# owl.net
KiCad netlist of a schematic drawn in EAGLE
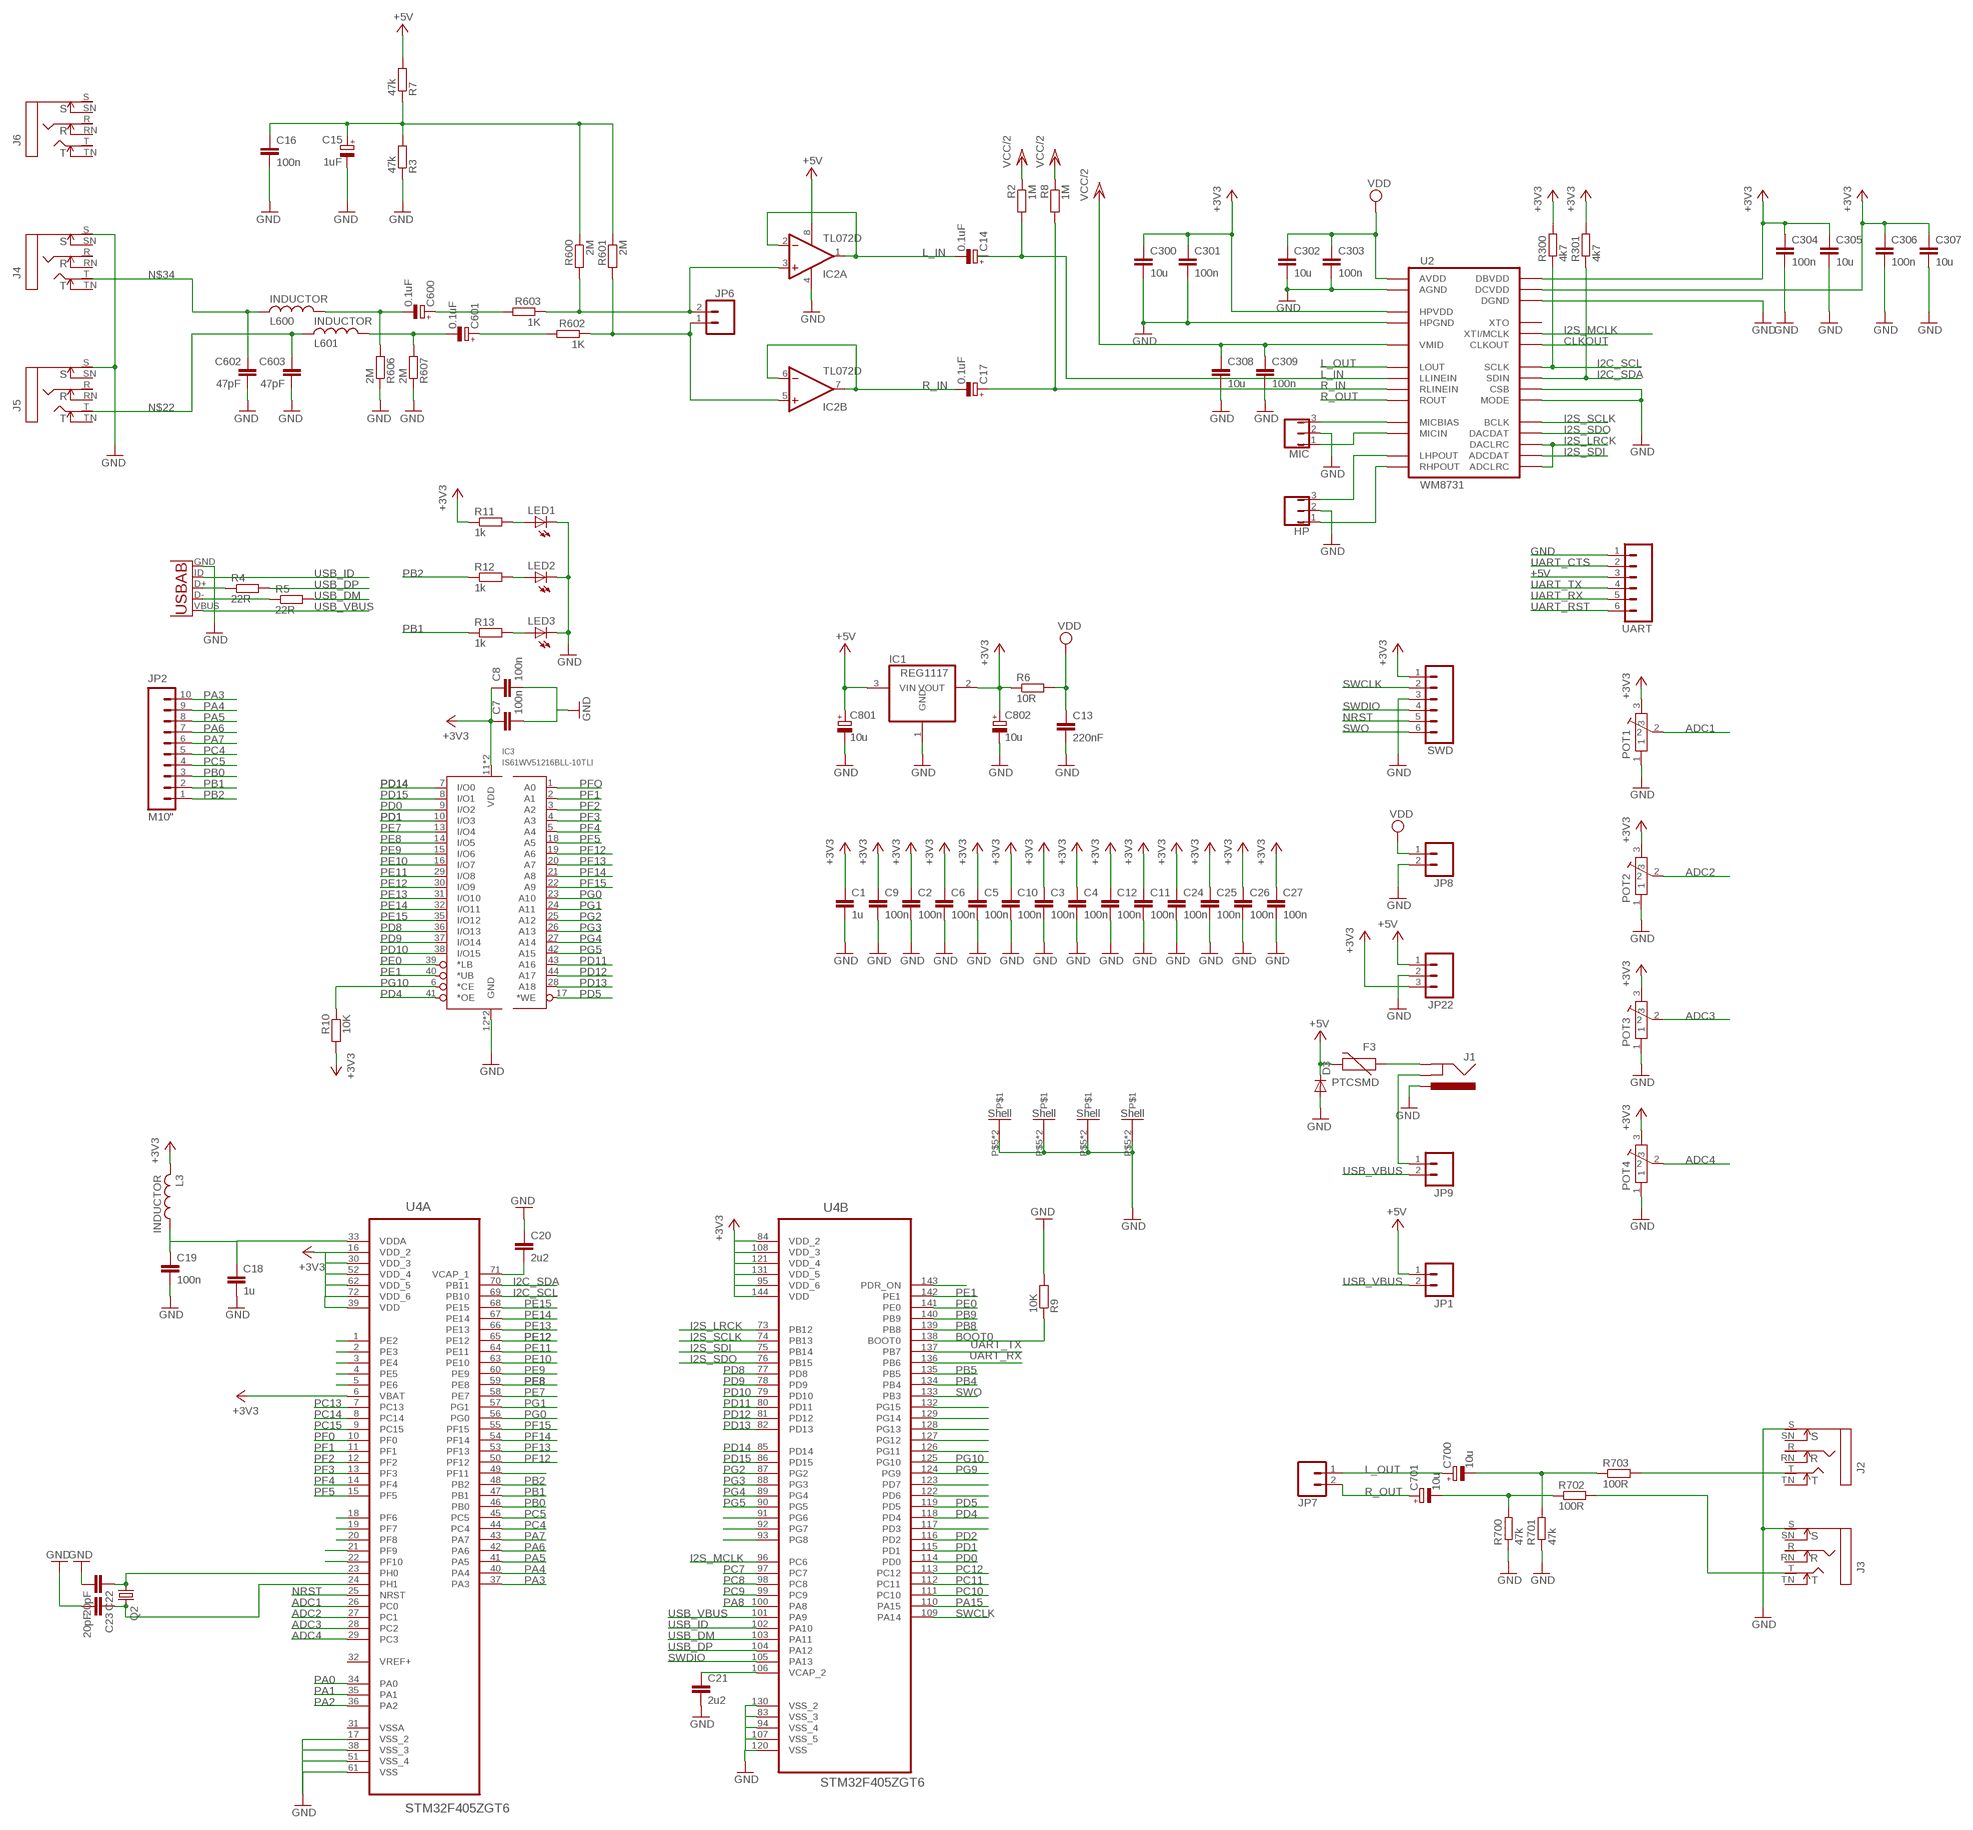
[diagram p0: schematic, sheet 1]

(export (version "E")
  (design (tool "Eeschema 10.0.6"))
  (components
    (comp (ref "C1")
      (value "1u")
      (footprint "eagle-import:C0603")
      (libsource (lib "eagle-import") (part "C-EUC0603"))
    )
    (comp (ref "C2")
      (value "100n")
      (footprint "eagle-import:C0603")
      (libsource (lib "eagle-import") (part "C-EUC0603"))
    )
    (comp (ref "C3")
      (value "100n")
      (footprint "eagle-import:C0603")
      (libsource (lib "eagle-import") (part "C-EUC0603"))
    )
    (comp (ref "C4")
      (value "100n")
      (footprint "eagle-import:C0603")
      (libsource (lib "eagle-import") (part "C-EUC0603"))
    )
    (comp (ref "C5")
      (value "100n")
      (footprint "eagle-import:C0603")
      (libsource (lib "eagle-import") (part "C-EUC0603"))
    )
    (comp (ref "C6")
      (value "100n")
      (footprint "eagle-import:C0603")
      (libsource (lib "eagle-import") (part "C-EUC0603"))
    )
    (comp (ref "C7")
      (value "100n")
      (footprint "eagle-import:C0603")
      (libsource (lib "eagle-import") (part "C-EUC0603"))
    )
    (comp (ref "C8")
      (value "100n")
      (footprint "eagle-import:C0603")
      (libsource (lib "eagle-import") (part "C-EUC0603"))
    )
    (comp (ref "C9")
      (value "100n")
      (footprint "eagle-import:C0603")
      (libsource (lib "eagle-import") (part "C-EUC0603"))
    )
    (comp (ref "C10")
      (value "100n")
      (footprint "eagle-import:C0603")
      (libsource (lib "eagle-import") (part "C-EUC0603"))
    )
    (comp (ref "C11")
      (value "100n")
      (footprint "eagle-import:C0603")
      (libsource (lib "eagle-import") (part "C-EUC0603"))
    )
    (comp (ref "C12")
      (value "100n")
      (footprint "eagle-import:C0603")
      (libsource (lib "eagle-import") (part "C-EUC0603"))
    )
    (comp (ref "C13")
      (value "220nF")
      (footprint "eagle-import:C0603")
      (libsource (lib "eagle-import") (part "C-EUC0603"))
    )
    (comp (ref "C14")
      (value "0.1uF")
      (footprint "eagle-import:PANASONIC_A")
      (libsource (lib "eagle-import") (part "CPOL-EUA"))
    )
    (comp (ref "C15")
      (value "1uF")
      (footprint "eagle-import:PANASONIC_A")
      (libsource (lib "eagle-import") (part "CPOL-EUA"))
    )
    (comp (ref "C16")
      (value "100n")
      (footprint "eagle-import:C0603")
      (libsource (lib "eagle-import") (part "C-EUC0603"))
    )
    (comp (ref "C17")
      (value "0.1uF")
      (footprint "eagle-import:PANASONIC_A")
      (libsource (lib "eagle-import") (part "CPOL-EUA"))
    )
    (comp (ref "C18")
      (value "1u")
      (footprint "eagle-import:C0603")
      (libsource (lib "eagle-import") (part "C-EUC0603"))
    )
    (comp (ref "C19")
      (value "100n")
      (footprint "eagle-import:C0603")
      (libsource (lib "eagle-import") (part "C-EUC0603"))
    )
    (comp (ref "C20")
      (value "2u2")
      (footprint "eagle-import:C0603")
      (libsource (lib "eagle-import") (part "C-EUC0603"))
    )
    (comp (ref "C21")
      (value "2u2")
      (footprint "eagle-import:C0603")
      (libsource (lib "eagle-import") (part "C-EUC0603"))
    )
    (comp (ref "C22")
      (value "20pF")
      (footprint "eagle-import:C0603")
      (libsource (lib "eagle-import") (part "C-EUC0603"))
    )
    (comp (ref "C23")
      (value "20pF")
      (footprint "eagle-import:C0603")
      (libsource (lib "eagle-import") (part "C-EUC0603"))
    )
    (comp (ref "C24")
      (value "100n")
      (footprint "eagle-import:C0603")
      (libsource (lib "eagle-import") (part "C-EUC0603"))
    )
    (comp (ref "C25")
      (value "100n")
      (footprint "eagle-import:C0603")
      (libsource (lib "eagle-import") (part "C-EUC0603"))
    )
    (comp (ref "C26")
      (value "100n")
      (footprint "eagle-import:C0603")
      (libsource (lib "eagle-import") (part "C-EUC0603"))
    )
    (comp (ref "C27")
      (value "100n")
      (footprint "eagle-import:C0603")
      (libsource (lib "eagle-import") (part "C-EUC0603"))
    )
    (comp (ref "C300")
      (value "10u")
      (footprint "eagle-import:C1206")
      (libsource (lib "eagle-import") (part "C-EUC1206"))
    )
    (comp (ref "C301")
      (value "100n")
      (footprint "eagle-import:C0603")
      (libsource (lib "eagle-import") (part "C-EUC0603"))
    )
    (comp (ref "C302")
      (value "10u")
      (footprint "eagle-import:C1206")
      (libsource (lib "eagle-import") (part "C-EUC1206"))
    )
    (comp (ref "C303")
      (value "100n")
      (footprint "eagle-import:C0603")
      (libsource (lib "eagle-import") (part "C-EUC0603"))
    )
    (comp (ref "C304")
      (value "100n")
      (footprint "eagle-import:C0603")
      (libsource (lib "eagle-import") (part "C-EUC0603"))
    )
    (comp (ref "C305")
      (value "10u")
      (footprint "eagle-import:C1206")
      (libsource (lib "eagle-import") (part "C-EUC1206"))
    )
    (comp (ref "C306")
      (value "100n")
      (footprint "eagle-import:C0603")
      (libsource (lib "eagle-import") (part "C-EUC0603"))
    )
    (comp (ref "C307")
      (value "10u")
      (footprint "eagle-import:C1206")
      (libsource (lib "eagle-import") (part "C-EUC1206"))
    )
    (comp (ref "C308")
      (value "10u")
      (footprint "eagle-import:C1206")
      (libsource (lib "eagle-import") (part "C-EUC1206"))
    )
    (comp (ref "C309")
      (value "100n")
      (footprint "eagle-import:C0603")
      (libsource (lib "eagle-import") (part "C-EUC0603"))
    )
    (comp (ref "C600")
      (value "0.1uF")
      (footprint "eagle-import:PANASONIC_A")
      (libsource (lib "eagle-import") (part "CPOL-EUA"))
    )
    (comp (ref "C601")
      (value "0.1uF")
      (footprint "eagle-import:PANASONIC_A")
      (libsource (lib "eagle-import") (part "CPOL-EUA"))
    )
    (comp (ref "C602")
      (value "47pF")
      (footprint "eagle-import:C0603")
      (libsource (lib "eagle-import") (part "C-EUC0603"))
    )
    (comp (ref "C603")
      (value "47pF")
      (footprint "eagle-import:C0603")
      (libsource (lib "eagle-import") (part "C-EUC0603"))
    )
    (comp (ref "C700")
      (value "10u")
      (footprint "eagle-import:PANASONIC_A")
      (libsource (lib "eagle-import") (part "CPOL-EUA"))
    )
    (comp (ref "C701")
      (value "10u")
      (footprint "eagle-import:PANASONIC_A")
      (libsource (lib "eagle-import") (part "CPOL-EUA"))
    )
    (comp (ref "C801")
      (value "10u")
      (footprint "eagle-import:PANASONIC_A")
      (libsource (lib "eagle-import") (part "CPOL-EUA"))
    )
    (comp (ref "C802")
      (value "10u")
      (footprint "eagle-import:PANASONIC_A")
      (libsource (lib "eagle-import") (part "CPOL-EUA"))
    )
    (comp (ref "D3")
      (value "DIODESMA")
      (footprint "eagle-import:SMA-DIODE")
      (libsource (lib "eagle-import") (part "DIODESMA"))
    )
    (comp (ref "F3")
      (value "PTCSMD")
      (footprint "eagle-import:PTC-1206")
      (libsource (lib "eagle-import") (part "PTCSMD"))
    )
    (comp (ref "HP")
      (value "JMP/3P/SIP")
      (footprint "eagle-import:JMP_3P_SIP")
      (libsource (lib "eagle-import") (part "JMP/3P/SIP"))
    )
    (comp (ref "IC1")
      (value "REG1117")
      (footprint "eagle-import:SOT223")
      (libsource (lib "eagle-import") (part "REG1117"))
    )
    (comp (ref "IC2")
      (value "TL072D")
      (footprint "eagle-import:SO08")
      (libsource (lib "eagle-import") (part "TL072D"))
    )
    (comp (ref "IC3")
      (value "IS61WV51216BLL-10TLI")
      (footprint "eagle-import:TSOP44-II")
      (libsource (lib "eagle-import") (part "IS61WV51216BLL-10TLI"))
    )
    (comp (ref "J1")
      (value "POWER_JACKPTH")
      (footprint "eagle-import:POWER_JACK_PTH")
      (libsource (lib "eagle-import") (part "POWER_JACKPTH"))
    )
    (comp (ref "J2")
      (value "NEUTRIK_NMJ6HCD2")
      (footprint "eagle-import:NMJ6HCD2")
      (libsource (lib "eagle-import") (part "NEUTRIK_NMJ6HCD2"))
    )
    (comp (ref "J3")
      (value "NEUTRIK_NMJ6HCD2")
      (footprint "eagle-import:NMJ6HCD2")
      (libsource (lib "eagle-import") (part "NEUTRIK_NMJ6HCD2"))
    )
    (comp (ref "J4")
      (value "NEUTRIK_NMJ6HCD2")
      (footprint "eagle-import:NMJ6HCD2")
      (libsource (lib "eagle-import") (part "NEUTRIK_NMJ6HCD2"))
    )
    (comp (ref "J5")
      (value "NEUTRIK_NMJ6HCD2")
      (footprint "eagle-import:NMJ6HCD2")
      (libsource (lib "eagle-import") (part "NEUTRIK_NMJ6HCD2"))
    )
    (comp (ref "J6")
      (value "NEUTRIK_NMJ6HCD2")
      (footprint "eagle-import:NMJ6HCD2")
      (libsource (lib "eagle-import") (part "NEUTRIK_NMJ6HCD2"))
    )
    (comp (ref "JP1")
      (value "M02PTH")
      (footprint "eagle-import:1X02")
      (libsource (lib "eagle-import") (part "M02PTH"))
    )
    (comp (ref "JP2")
      (value "M10\"")
      (footprint "eagle-import:1X10")
      (libsource (lib "eagle-import") (part "M10{dblquote}"))
    )
    (comp (ref "JP6")
      (value "M02PTH")
      (footprint "eagle-import:1X02")
      (libsource (lib "eagle-import") (part "M02PTH"))
    )
    (comp (ref "JP7")
      (value "M02PTH")
      (footprint "eagle-import:1X02")
      (libsource (lib "eagle-import") (part "M02PTH"))
    )
    (comp (ref "JP8")
      (value "M02PTH")
      (footprint "eagle-import:1X02")
      (libsource (lib "eagle-import") (part "M02PTH"))
    )
    (comp (ref "JP9")
      (value "M02PTH")
      (footprint "eagle-import:1X02")
      (libsource (lib "eagle-import") (part "M02PTH"))
    )
    (comp (ref "JP22")
      (value "M03PTH")
      (footprint "eagle-import:1X03")
      (libsource (lib "eagle-import") (part "M03PTH"))
    )
    (comp (ref "L3")
      (value "INDUCTOR")
      (footprint "eagle-import:0603")
      (libsource (lib "eagle-import") (part "INDUCTOR"))
    )
    (comp (ref "L600")
      (value "INDUCTOR")
      (footprint "eagle-import:0603")
      (libsource (lib "eagle-import") (part "INDUCTOR"))
    )
    (comp (ref "L601")
      (value "INDUCTOR")
      (footprint "eagle-import:0603")
      (libsource (lib "eagle-import") (part "INDUCTOR"))
    )
    (comp (ref "LED1")
      (value "LED1206")
      (footprint "eagle-import:LED-1206")
      (libsource (lib "eagle-import") (part "LED1206"))
    )
    (comp (ref "LED2")
      (value "LED1206")
      (footprint "eagle-import:LED-1206")
      (libsource (lib "eagle-import") (part "LED1206"))
    )
    (comp (ref "LED3")
      (value "LED3MM")
      (footprint "eagle-import:LED3MM")
      (libsource (lib "eagle-import") (part "LED3MM"))
    )
    (comp (ref "MIC")
      (value "JMP/3P/SIP")
      (footprint "eagle-import:JMP_3P_SIP")
      (libsource (lib "eagle-import") (part "JMP/3P/SIP"))
    )
    (comp (ref "POT1")
      (value "POT-ALPS-RK09L1140")
      (footprint "eagle-import:POT-ALPS-RK09L1140")
      (libsource (lib "eagle-import") (part "POT-ALPS-RK09L1140"))
    )
    (comp (ref "POT2")
      (value "POT-ALPS-RK09L1140")
      (footprint "eagle-import:POT-ALPS-RK09L1140")
      (libsource (lib "eagle-import") (part "POT-ALPS-RK09L1140"))
    )
    (comp (ref "POT3")
      (value "POT-ALPS-RK09L1140")
      (footprint "eagle-import:POT-ALPS-RK09L1140")
      (libsource (lib "eagle-import") (part "POT-ALPS-RK09L1140"))
    )
    (comp (ref "POT4")
      (value "POT-ALPS-RK09L1140")
      (footprint "eagle-import:POT-ALPS-RK09L1140")
      (libsource (lib "eagle-import") (part "POT-ALPS-RK09L1140"))
    )
    (comp (ref "Q2")
      (value "CRYSTALHC49UP")
      (footprint "eagle-import:HC49UP")
      (libsource (lib "eagle-import") (part "CRYSTALHC49UP"))
    )
    (comp (ref "R2")
      (value "1M")
      (footprint "eagle-import:R0603")
      (libsource (lib "eagle-import") (part "R-EU_R0603"))
    )
    (comp (ref "R3")
      (value "47k")
      (footprint "eagle-import:R0603")
      (libsource (lib "eagle-import") (part "R-EU_R0603"))
    )
    (comp (ref "R4")
      (value "22R")
      (footprint "eagle-import:R0603")
      (libsource (lib "eagle-import") (part "R-EU_R0603"))
    )
    (comp (ref "R5")
      (value "22R")
      (footprint "eagle-import:R0603")
      (libsource (lib "eagle-import") (part "R-EU_R0603"))
    )
    (comp (ref "R6")
      (value "10R")
      (footprint "eagle-import:R0603")
      (libsource (lib "eagle-import") (part "R-EU_R0603"))
    )
    (comp (ref "R7")
      (value "47k")
      (footprint "eagle-import:R0603")
      (libsource (lib "eagle-import") (part "R-EU_R0603"))
    )
    (comp (ref "R8")
      (value "1M")
      (footprint "eagle-import:R0603")
      (libsource (lib "eagle-import") (part "R-EU_R0603"))
    )
    (comp (ref "R9")
      (value "10K")
      (footprint "eagle-import:R0603")
      (libsource (lib "eagle-import") (part "R-EU_R0603"))
    )
    (comp (ref "R10")
      (value "10K")
      (footprint "eagle-import:R0603")
      (libsource (lib "eagle-import") (part "R-EU_R0603"))
    )
    (comp (ref "R11")
      (value "1k")
      (footprint "eagle-import:R0603")
      (libsource (lib "eagle-import") (part "R-EU_R0603"))
    )
    (comp (ref "R12")
      (value "1k")
      (footprint "eagle-import:R0603")
      (libsource (lib "eagle-import") (part "R-EU_R0603"))
    )
    (comp (ref "R13")
      (value "1k")
      (footprint "eagle-import:R0603")
      (libsource (lib "eagle-import") (part "R-EU_R0603"))
    )
    (comp (ref "R300")
      (value "4k7")
      (footprint "eagle-import:R0603")
      (libsource (lib "eagle-import") (part "R-EU_R0603"))
    )
    (comp (ref "R301")
      (value "4k7")
      (footprint "eagle-import:R0603")
      (libsource (lib "eagle-import") (part "R-EU_R0603"))
    )
    (comp (ref "R600")
      (value "2M")
      (footprint "eagle-import:R0603")
      (libsource (lib "eagle-import") (part "R-EU_R0603"))
    )
    (comp (ref "R601")
      (value "2M")
      (footprint "eagle-import:R0603")
      (libsource (lib "eagle-import") (part "R-EU_R0603"))
    )
    (comp (ref "R602")
      (value "1K")
      (footprint "eagle-import:R0603")
      (libsource (lib "eagle-import") (part "R-EU_R0603"))
    )
    (comp (ref "R603")
      (value "1K")
      (footprint "eagle-import:R0603")
      (libsource (lib "eagle-import") (part "R-EU_R0603"))
    )
    (comp (ref "R606")
      (value "2M")
      (footprint "eagle-import:R0603")
      (libsource (lib "eagle-import") (part "R-EU_R0603"))
    )
    (comp (ref "R607")
      (value "2M")
      (footprint "eagle-import:R0603")
      (libsource (lib "eagle-import") (part "R-EU_R0603"))
    )
    (comp (ref "R700")
      (value "47k")
      (footprint "eagle-import:R0603")
      (libsource (lib "eagle-import") (part "R-EU_R0603"))
    )
    (comp (ref "R701")
      (value "47k")
      (footprint "eagle-import:R0603")
      (libsource (lib "eagle-import") (part "R-EU_R0603"))
    )
    (comp (ref "R702")
      (value "100R")
      (footprint "eagle-import:R0603")
      (libsource (lib "eagle-import") (part "R-EU_R0603"))
    )
    (comp (ref "R703")
      (value "100R")
      (footprint "eagle-import:R0603")
      (libsource (lib "eagle-import") (part "R-EU_R0603"))
    )
    (comp (ref "SWD")
      (value "M06SIP")
      (footprint "eagle-import:1X06")
      (libsource (lib "eagle-import") (part "M06SIP"))
    )
    (comp (ref "U2")
      (value "WM8731")
      (footprint "eagle-import:28-SSOP")
      (libsource (lib "eagle-import") (part "WM8731"))
    )
    (comp (ref "U3")
      (value "USB-AB")
      (footprint "eagle-import:USB-AB-MICRO-SMD")
      (libsource (lib "eagle-import") (part "USB-AB"))
    )
    (comp (ref "U4")
      (value "STM32F405ZGT6")
      (footprint "eagle-import:QFP50P2200X2200X160-144N")
      (libsource (lib "eagle-import") (part "STM32F405ZGT6"))
    )
    (comp (ref "UART")
      (value "M06SIP")
      (footprint "eagle-import:1X06")
      (libsource (lib "eagle-import") (part "M06SIP"))
    )
  )
  (nets
    (net (code "1") (name "+3V3") (class "Default")
      (node (ref "C1") (pin "1") (pinfunction "1_1") (pintype "passive"))
      (node (ref "C10") (pin "1") (pinfunction "1_1") (pintype "passive"))
      (node (ref "C11") (pin "1") (pinfunction "1_1") (pintype "passive"))
      (node (ref "C12") (pin "1") (pinfunction "1_1") (pintype "passive"))
      (node (ref "C2") (pin "1") (pinfunction "1_1") (pintype "passive"))
      (node (ref "C24") (pin "1") (pinfunction "1_1") (pintype "passive"))
      (node (ref "C25") (pin "1") (pinfunction "1_1") (pintype "passive"))
      (node (ref "C26") (pin "1") (pinfunction "1_1") (pintype "passive"))
      (node (ref "C27") (pin "1") (pinfunction "1_1") (pintype "passive"))
      (node (ref "C3") (pin "1") (pinfunction "1_1") (pintype "passive"))
      (node (ref "C300") (pin "1") (pinfunction "1_1") (pintype "passive"))
      (node (ref "C301") (pin "1") (pinfunction "1_1") (pintype "passive"))
      (node (ref "C304") (pin "1") (pinfunction "1_1") (pintype "passive"))
      (node (ref "C305") (pin "1") (pinfunction "1_1") (pintype "passive"))
      (node (ref "C306") (pin "1") (pinfunction "1_1") (pintype "passive"))
      (node (ref "C307") (pin "1") (pinfunction "1_1") (pintype "passive"))
      (node (ref "C4") (pin "1") (pinfunction "1_1") (pintype "passive"))
      (node (ref "C5") (pin "1") (pinfunction "1_1") (pintype "passive"))
      (node (ref "C6") (pin "1") (pinfunction "1_1") (pintype "passive"))
      (node (ref "C7") (pin "1") (pinfunction "1_1") (pintype "passive"))
      (node (ref "C8") (pin "1") (pinfunction "1_1") (pintype "passive"))
      (node (ref "C802") (pin "+") (pinfunction "+_+") (pintype "passive"))
      (node (ref "C9") (pin "1") (pinfunction "1_1") (pintype "passive"))
      (node (ref "IC1") (pin "2") (pinfunction "VOUT_2") (pintype "output"))
      (node (ref "IC3") (pin "11") (pinfunction "VDD_11") (pintype "power_in"))
      (node (ref "IC3") (pin "33") (pinfunction "VDD_33") (pintype "power_in"))
      (node (ref "JP22") (pin "3") (pinfunction "3_3") (pintype "passive"))
      (node (ref "L3") (pin "2") (pinfunction "2_2") (pintype "passive"))
      (node (ref "POT1") (pin "3") (pinfunction "3_3") (pintype "bidirectional"))
      (node (ref "POT2") (pin "3") (pinfunction "3_3") (pintype "bidirectional"))
      (node (ref "POT3") (pin "3") (pinfunction "3_3") (pintype "bidirectional"))
      (node (ref "POT4") (pin "3") (pinfunction "3_3") (pintype "bidirectional"))
      (node (ref "R10") (pin "2") (pinfunction "2_2") (pintype "passive"))
      (node (ref "R11") (pin "1") (pinfunction "1_1") (pintype "passive"))
      (node (ref "R300") (pin "2") (pinfunction "2_2") (pintype "passive"))
      (node (ref "R301") (pin "2") (pinfunction "2_2") (pintype "passive"))
      (node (ref "R6") (pin "1") (pinfunction "1_1") (pintype "passive"))
      (node (ref "SWD") (pin "1") (pinfunction "1_1") (pintype "passive"))
      (node (ref "U2") (pin "P$1") (pinfunction "DBVDD_P$1") (pintype "power_in"))
      (node (ref "U2") (pin "P$27") (pinfunction "DCVDD_P$27") (pintype "power_in"))
      (node (ref "U2") (pin "P$8") (pinfunction "HPVDD_P$8") (pintype "power_in"))
      (node (ref "U4") (pin "108") (pinfunction "VDD_3_108") (pintype "power_in"))
      (node (ref "U4") (pin "121") (pinfunction "VDD_4_121") (pintype "power_in"))
      (node (ref "U4") (pin "131") (pinfunction "VDD_5_131") (pintype "power_in"))
      (node (ref "U4") (pin "144") (pinfunction "VDD_144") (pintype "power_in"))
      (node (ref "U4") (pin "16") (pinfunction "VDD_2_16") (pintype "power_in"))
      (node (ref "U4") (pin "30") (pinfunction "VDD_3_30") (pintype "power_in"))
      (node (ref "U4") (pin "39") (pinfunction "VDD_39") (pintype "power_in"))
      (node (ref "U4") (pin "52") (pinfunction "VDD_4_52") (pintype "power_in"))
      (node (ref "U4") (pin "6") (pinfunction "VBAT_6") (pintype "passive"))
      (node (ref "U4") (pin "62") (pinfunction "VDD_5_62") (pintype "power_in"))
      (node (ref "U4") (pin "72") (pinfunction "VDD_6_72") (pintype "power_in"))
      (node (ref "U4") (pin "84") (pinfunction "VDD_2_84") (pintype "power_in"))
      (node (ref "U4") (pin "95") (pinfunction "VDD_6_95") (pintype "power_in"))
    )
    (net (code "2") (name "+5V") (class "Default")
      (node (ref "C801") (pin "+") (pinfunction "+_+") (pintype "passive"))
      (node (ref "D3") (pin "C") (pinfunction "C_C") (pintype "passive"))
      (node (ref "F3") (pin "2") (pinfunction "2_2") (pintype "bidirectional"))
      (node (ref "IC1") (pin "3") (pinfunction "VIN_3") (pintype "input"))
      (node (ref "IC2") (pin "8") (pinfunction "V+_8") (pintype "power_in"))
      (node (ref "JP1") (pin "1") (pinfunction "1_1") (pintype "passive"))
      (node (ref "JP22") (pin "1") (pinfunction "1_1") (pintype "passive"))
      (node (ref "R7") (pin "2") (pinfunction "2_2") (pintype "passive"))
      (node (ref "UART") (pin "3") (pinfunction "3_3") (pintype "passive"))
    )
    (net (code "3") (name "/ADC1") (class "Default")
      (node (ref "POT1") (pin "2") (pinfunction "2_2") (pintype "bidirectional"))
      (node (ref "U4") (pin "26") (pinfunction "PC0_26") (pintype "bidirectional"))
    )
    (net (code "4") (name "/ADC2") (class "Default")
      (node (ref "POT2") (pin "2") (pinfunction "2_2") (pintype "bidirectional"))
      (node (ref "U4") (pin "27") (pinfunction "PC1_27") (pintype "bidirectional"))
    )
    (net (code "5") (name "/ADC3") (class "Default")
      (node (ref "POT3") (pin "2") (pinfunction "2_2") (pintype "bidirectional"))
      (node (ref "U4") (pin "28") (pinfunction "PC2_28") (pintype "bidirectional"))
    )
    (net (code "6") (name "/ADC4") (class "Default")
      (node (ref "POT4") (pin "2") (pinfunction "2_2") (pintype "bidirectional"))
      (node (ref "U4") (pin "29") (pinfunction "PC3_29") (pintype "bidirectional"))
    )
    (net (code "7") (name "/BOOT0") (class "Default")
      (node (ref "R9") (pin "1") (pinfunction "1_1") (pintype "passive"))
      (node (ref "U4") (pin "138") (pinfunction "BOOT0_138") (pintype "passive"))
    )
    (net (code "8") (name "/CLKOUT") (class "Default")
      (node (ref "U2") (pin "P$2") (pinfunction "CLKOUT_P$2") (pintype "output"))
    )
    (net (code "9") (name "/I2C_SCL") (class "Default")
      (node (ref "R300") (pin "1") (pinfunction "1_1") (pintype "passive"))
      (node (ref "U2") (pin "P$24") (pinfunction "SCLK_P$24") (pintype "input"))
      (node (ref "U4") (pin "69") (pinfunction "PB10_69") (pintype "bidirectional"))
    )
    (net (code "10") (name "/I2C_SDA") (class "Default")
      (node (ref "R301") (pin "1") (pinfunction "1_1") (pintype "passive"))
      (node (ref "U2") (pin "P$23") (pinfunction "SDIN_P$23") (pintype "bidirectional"))
      (node (ref "U4") (pin "70") (pinfunction "PB11_70") (pintype "bidirectional"))
    )
    (net (code "11") (name "/I2S_LRCK") (class "Default")
      (node (ref "U2") (pin "P$5") (pinfunction "DACLRC_P$5") (pintype "bidirectional"))
      (node (ref "U2") (pin "P$7") (pinfunction "ADCLRC_P$7") (pintype "bidirectional"))
      (node (ref "U4") (pin "73") (pinfunction "PB12_73") (pintype "bidirectional"))
    )
    (net (code "12") (name "/I2S_MCLK") (class "Default")
      (node (ref "U2") (pin "P$25") (pinfunction "XTI/MCLK_P$25") (pintype "input"))
      (node (ref "U4") (pin "96") (pinfunction "PC6_96") (pintype "bidirectional"))
    )
    (net (code "13") (name "/I2S_SCLK") (class "Default")
      (node (ref "U2") (pin "P$3") (pinfunction "BCLK_P$3") (pintype "bidirectional"))
      (node (ref "U4") (pin "74") (pinfunction "PB13_74") (pintype "bidirectional"))
    )
    (net (code "14") (name "/I2S_SDI") (class "Default")
      (node (ref "U2") (pin "P$6") (pinfunction "ADCDAT_P$6") (pintype "output"))
      (node (ref "U4") (pin "75") (pinfunction "PB14_75") (pintype "bidirectional"))
    )
    (net (code "15") (name "/I2S_SDO") (class "Default")
      (node (ref "U2") (pin "P$4") (pinfunction "DACDAT_P$4") (pintype "input"))
      (node (ref "U4") (pin "76") (pinfunction "PB15_76") (pintype "bidirectional"))
    )
    (net (code "16") (name "/L_IN") (class "Default")
      (node (ref "C14") (pin "-") (pinfunction "-_-") (pintype "passive"))
      (node (ref "IC2") (pin "1") (pinfunction "OUT_1") (pintype "output"))
      (node (ref "IC2") (pin "2") (pinfunction "-IN_2") (pintype "input"))
      (node (ref "R2") (pin "2") (pinfunction "2_2") (pintype "passive"))
      (node (ref "U2") (pin "P$20") (pinfunction "LLINEIN_P$20") (pintype "input"))
    )
    (net (code "17") (name "/L_OUT") (class "Default")
      (node (ref "C700") (pin "+") (pinfunction "+_+") (pintype "passive"))
      (node (ref "JP7") (pin "1") (pinfunction "1_1") (pintype "passive"))
      (node (ref "U2") (pin "P$12") (pinfunction "LOUT_P$12") (pintype "output"))
    )
    (net (code "18") (name "/N$22") (class "Default")
      (node (ref "C603") (pin "1") (pinfunction "1_1") (pintype "passive"))
      (node (ref "J5") (pin "T") (pinfunction "T_T") (pintype "passive"))
      (node (ref "L601") (pin "2") (pinfunction "2_2") (pintype "passive"))
    )
    (net (code "19") (name "/N$34") (class "Default")
      (node (ref "C602") (pin "1") (pinfunction "1_1") (pintype "passive"))
      (node (ref "J4") (pin "T") (pinfunction "T_T") (pintype "passive"))
      (node (ref "L600") (pin "2") (pinfunction "2_2") (pintype "passive"))
    )
    (net (code "20") (name "/NRST") (class "Default")
      (node (ref "SWD") (pin "5") (pinfunction "5_5") (pintype "passive"))
      (node (ref "U4") (pin "25") (pinfunction "NRST_25") (pintype "passive"))
    )
    (net (code "21") (name "/PA0") (class "Default")
      (node (ref "U4") (pin "34") (pinfunction "PA0_34") (pintype "bidirectional"))
    )
    (net (code "22") (name "/PA1") (class "Default")
      (node (ref "U4") (pin "35") (pinfunction "PA1_35") (pintype "bidirectional"))
    )
    (net (code "23") (name "/PA2") (class "Default")
      (node (ref "U4") (pin "36") (pinfunction "PA2_36") (pintype "bidirectional"))
    )
    (net (code "24") (name "/PA3") (class "Default")
      (node (ref "JP2") (pin "10") (pinfunction "10_10") (pintype "passive"))
      (node (ref "U4") (pin "37") (pinfunction "PA3_37") (pintype "bidirectional"))
    )
    (net (code "25") (name "/PA4") (class "Default")
      (node (ref "JP2") (pin "9") (pinfunction "9_9") (pintype "passive"))
      (node (ref "U4") (pin "40") (pinfunction "PA4_40") (pintype "bidirectional"))
    )
    (net (code "26") (name "/PA5") (class "Default")
      (node (ref "JP2") (pin "8") (pinfunction "8_8") (pintype "passive"))
      (node (ref "U4") (pin "41") (pinfunction "PA5_41") (pintype "bidirectional"))
    )
    (net (code "27") (name "/PA6") (class "Default")
      (node (ref "JP2") (pin "7") (pinfunction "7_7") (pintype "passive"))
      (node (ref "U4") (pin "42") (pinfunction "PA6_42") (pintype "bidirectional"))
    )
    (net (code "28") (name "/PA7") (class "Default")
      (node (ref "JP2") (pin "6") (pinfunction "6_6") (pintype "passive"))
      (node (ref "U4") (pin "43") (pinfunction "PA7_43") (pintype "bidirectional"))
    )
    (net (code "29") (name "/PA8") (class "Default")
      (node (ref "U4") (pin "100") (pinfunction "PA8_100") (pintype "bidirectional"))
    )
    (net (code "30") (name "/PA15") (class "Default")
      (node (ref "U4") (pin "110") (pinfunction "PA15_110") (pintype "bidirectional"))
    )
    (net (code "31") (name "/PB0") (class "Default")
      (node (ref "JP2") (pin "3") (pinfunction "3_3") (pintype "passive"))
      (node (ref "U4") (pin "46") (pinfunction "PB0_46") (pintype "bidirectional"))
    )
    (net (code "32") (name "/PB1") (class "Default")
      (node (ref "JP2") (pin "2") (pinfunction "2_2") (pintype "passive"))
      (node (ref "R13") (pin "1") (pinfunction "1_1") (pintype "passive"))
      (node (ref "U4") (pin "47") (pinfunction "PB1_47") (pintype "bidirectional"))
    )
    (net (code "33") (name "/PB2") (class "Default")
      (node (ref "JP2") (pin "1") (pinfunction "1_1") (pintype "passive"))
      (node (ref "R12") (pin "1") (pinfunction "1_1") (pintype "passive"))
      (node (ref "U4") (pin "48") (pinfunction "PB2_48") (pintype "bidirectional"))
    )
    (net (code "34") (name "/PB4") (class "Default")
      (node (ref "U4") (pin "134") (pinfunction "PB4_134") (pintype "bidirectional"))
    )
    (net (code "35") (name "/PB5") (class "Default")
      (node (ref "U4") (pin "135") (pinfunction "PB5_135") (pintype "bidirectional"))
    )
    (net (code "36") (name "/PB8") (class "Default")
      (node (ref "U4") (pin "139") (pinfunction "PB8_139") (pintype "bidirectional"))
    )
    (net (code "37") (name "/PB9") (class "Default")
      (node (ref "U4") (pin "140") (pinfunction "PB9_140") (pintype "bidirectional"))
    )
    (net (code "38") (name "/PC4") (class "Default")
      (node (ref "JP2") (pin "5") (pinfunction "5_5") (pintype "passive"))
      (node (ref "U4") (pin "44") (pinfunction "PC4_44") (pintype "bidirectional"))
    )
    (net (code "39") (name "/PC5") (class "Default")
      (node (ref "JP2") (pin "4") (pinfunction "4_4") (pintype "passive"))
      (node (ref "U4") (pin "45") (pinfunction "PC5_45") (pintype "bidirectional"))
    )
    (net (code "40") (name "/PC7") (class "Default")
      (node (ref "U4") (pin "97") (pinfunction "PC7_97") (pintype "bidirectional"))
    )
    (net (code "41") (name "/PC8") (class "Default")
      (node (ref "U4") (pin "98") (pinfunction "PC8_98") (pintype "bidirectional"))
    )
    (net (code "42") (name "/PC9") (class "Default")
      (node (ref "U4") (pin "99") (pinfunction "PC9_99") (pintype "bidirectional"))
    )
    (net (code "43") (name "/PC10") (class "Default")
      (node (ref "U4") (pin "111") (pinfunction "PC10_111") (pintype "bidirectional"))
    )
    (net (code "44") (name "/PC11") (class "Default")
      (node (ref "U4") (pin "112") (pinfunction "PC11_112") (pintype "bidirectional"))
    )
    (net (code "45") (name "/PC12") (class "Default")
      (node (ref "U4") (pin "113") (pinfunction "PC12_113") (pintype "bidirectional"))
    )
    (net (code "46") (name "/PC13") (class "Default")
      (node (ref "U4") (pin "7") (pinfunction "PC13_7") (pintype "bidirectional"))
    )
    (net (code "47") (name "/PC14") (class "Default")
      (node (ref "U4") (pin "8") (pinfunction "PC14_8") (pintype "bidirectional"))
    )
    (net (code "48") (name "/PC15") (class "Default")
      (node (ref "U4") (pin "9") (pinfunction "PC15_9") (pintype "bidirectional"))
    )
    (net (code "49") (name "/PD0") (class "Default")
      (node (ref "IC3") (pin "9") (pinfunction "I/O2_9") (pintype "bidirectional"))
      (node (ref "U4") (pin "114") (pinfunction "PD0_114") (pintype "bidirectional"))
    )
    (net (code "50") (name "/PD1") (class "Default")
      (node (ref "IC3") (pin "10") (pinfunction "I/O3_10") (pintype "bidirectional"))
      (node (ref "U4") (pin "115") (pinfunction "PD1_115") (pintype "bidirectional"))
    )
    (net (code "51") (name "/PD2") (class "Default")
      (node (ref "U4") (pin "116") (pinfunction "PD2_116") (pintype "bidirectional"))
    )
    (net (code "52") (name "/PD4") (class "Default")
      (node (ref "IC3") (pin "41") (pinfunction "*OE_41") (pintype "bidirectional"))
      (node (ref "U4") (pin "118") (pinfunction "PD4_118") (pintype "bidirectional"))
    )
    (net (code "53") (name "/PD5") (class "Default")
      (node (ref "IC3") (pin "17") (pinfunction "*WE_17") (pintype "bidirectional"))
      (node (ref "U4") (pin "119") (pinfunction "PD5_119") (pintype "bidirectional"))
    )
    (net (code "54") (name "/PD8") (class "Default")
      (node (ref "IC3") (pin "36") (pinfunction "I/O13_36") (pintype "bidirectional"))
      (node (ref "U4") (pin "77") (pinfunction "PD8_77") (pintype "bidirectional"))
    )
    (net (code "55") (name "/PD9") (class "Default")
      (node (ref "IC3") (pin "37") (pinfunction "I/O14_37") (pintype "bidirectional"))
      (node (ref "U4") (pin "78") (pinfunction "PD9_78") (pintype "bidirectional"))
    )
    (net (code "56") (name "/PD10") (class "Default")
      (node (ref "IC3") (pin "38") (pinfunction "I/O15_38") (pintype "bidirectional"))
      (node (ref "U4") (pin "79") (pinfunction "PD10_79") (pintype "bidirectional"))
    )
    (net (code "57") (name "/PD11") (class "Default")
      (node (ref "IC3") (pin "43") (pinfunction "A16_43") (pintype "input"))
      (node (ref "U4") (pin "80") (pinfunction "PD11_80") (pintype "bidirectional"))
    )
    (net (code "58") (name "/PD12") (class "Default")
      (node (ref "IC3") (pin "44") (pinfunction "A17_44") (pintype "input"))
      (node (ref "U4") (pin "81") (pinfunction "PD12_81") (pintype "bidirectional"))
    )
    (net (code "59") (name "/PD13") (class "Default")
      (node (ref "IC3") (pin "28") (pinfunction "A18_28") (pintype "input"))
      (node (ref "U4") (pin "82") (pinfunction "PD13_82") (pintype "bidirectional"))
    )
    (net (code "60") (name "/PD14") (class "Default")
      (node (ref "IC3") (pin "7") (pinfunction "I/O0_7") (pintype "bidirectional"))
      (node (ref "U4") (pin "85") (pinfunction "PD14_85") (pintype "bidirectional"))
    )
    (net (code "61") (name "/PD15") (class "Default")
      (node (ref "IC3") (pin "8") (pinfunction "I/O1_8") (pintype "bidirectional"))
      (node (ref "U4") (pin "86") (pinfunction "PD15_86") (pintype "bidirectional"))
    )
    (net (code "62") (name "/PE0") (class "Default")
      (node (ref "IC3") (pin "39") (pinfunction "*LB_39") (pintype "bidirectional"))
      (node (ref "U4") (pin "141") (pinfunction "PE0_141") (pintype "bidirectional"))
    )
    (net (code "63") (name "/PE1") (class "Default")
      (node (ref "IC3") (pin "40") (pinfunction "*UB_40") (pintype "bidirectional"))
      (node (ref "U4") (pin "142") (pinfunction "PE1_142") (pintype "bidirectional"))
    )
    (net (code "64") (name "/PE7") (class "Default")
      (node (ref "IC3") (pin "13") (pinfunction "I/O4_13") (pintype "bidirectional"))
      (node (ref "U4") (pin "58") (pinfunction "PE7_58") (pintype "bidirectional"))
    )
    (net (code "65") (name "/PE8") (class "Default")
      (node (ref "IC3") (pin "14") (pinfunction "I/O5_14") (pintype "bidirectional"))
      (node (ref "U4") (pin "59") (pinfunction "PE8_59") (pintype "bidirectional"))
    )
    (net (code "66") (name "/PE9") (class "Default")
      (node (ref "IC3") (pin "15") (pinfunction "I/O6_15") (pintype "bidirectional"))
      (node (ref "U4") (pin "60") (pinfunction "PE9_60") (pintype "bidirectional"))
    )
    (net (code "67") (name "/PE10") (class "Default")
      (node (ref "IC3") (pin "16") (pinfunction "I/O7_16") (pintype "bidirectional"))
      (node (ref "U4") (pin "63") (pinfunction "PE10_63") (pintype "bidirectional"))
    )
    (net (code "68") (name "/PE11") (class "Default")
      (node (ref "IC3") (pin "29") (pinfunction "I/O8_29") (pintype "bidirectional"))
      (node (ref "U4") (pin "64") (pinfunction "PE11_64") (pintype "bidirectional"))
    )
    (net (code "69") (name "/PE12") (class "Default")
      (node (ref "IC3") (pin "30") (pinfunction "I/O9_30") (pintype "bidirectional"))
      (node (ref "U4") (pin "65") (pinfunction "PE12_65") (pintype "bidirectional"))
    )
    (net (code "70") (name "/PE13") (class "Default")
      (node (ref "IC3") (pin "31") (pinfunction "I/O10_31") (pintype "bidirectional"))
      (node (ref "U4") (pin "66") (pinfunction "PE13_66") (pintype "bidirectional"))
    )
    (net (code "71") (name "/PE14") (class "Default")
      (node (ref "IC3") (pin "32") (pinfunction "I/O11_32") (pintype "bidirectional"))
      (node (ref "U4") (pin "67") (pinfunction "PE14_67") (pintype "bidirectional"))
    )
    (net (code "72") (name "/PE15") (class "Default")
      (node (ref "IC3") (pin "35") (pinfunction "I/O12_35") (pintype "bidirectional"))
      (node (ref "U4") (pin "68") (pinfunction "PE15_68") (pintype "bidirectional"))
    )
    (net (code "73") (name "/PF0") (class "Default")
      (node (ref "U4") (pin "10") (pinfunction "PF0_10") (pintype "bidirectional"))
    )
    (net (code "74") (name "/PF1") (class "Default")
      (node (ref "IC3") (pin "2") (pinfunction "A1_2") (pintype "input"))
      (node (ref "U4") (pin "11") (pinfunction "PF1_11") (pintype "bidirectional"))
    )
    (net (code "75") (name "/PF2") (class "Default")
      (node (ref "IC3") (pin "3") (pinfunction "A2_3") (pintype "input"))
      (node (ref "U4") (pin "12") (pinfunction "PF2_12") (pintype "bidirectional"))
    )
    (net (code "76") (name "/PF3") (class "Default")
      (node (ref "IC3") (pin "4") (pinfunction "A3_4") (pintype "input"))
      (node (ref "U4") (pin "13") (pinfunction "PF3_13") (pintype "bidirectional"))
    )
    (net (code "77") (name "/PF4") (class "Default")
      (node (ref "IC3") (pin "5") (pinfunction "A4_5") (pintype "input"))
      (node (ref "U4") (pin "14") (pinfunction "PF4_14") (pintype "bidirectional"))
    )
    (net (code "78") (name "/PF5") (class "Default")
      (node (ref "IC3") (pin "18") (pinfunction "A5_18") (pintype "input"))
      (node (ref "U4") (pin "15") (pinfunction "PF5_15") (pintype "bidirectional"))
    )
    (net (code "79") (name "/PF12") (class "Default")
      (node (ref "IC3") (pin "19") (pinfunction "A6_19") (pintype "input"))
      (node (ref "U4") (pin "50") (pinfunction "PF12_50") (pintype "bidirectional"))
    )
    (net (code "80") (name "/PF13") (class "Default")
      (node (ref "IC3") (pin "20") (pinfunction "A7_20") (pintype "input"))
      (node (ref "U4") (pin "53") (pinfunction "PF13_53") (pintype "bidirectional"))
    )
    (net (code "81") (name "/PF14") (class "Default")
      (node (ref "IC3") (pin "21") (pinfunction "A8_21") (pintype "input"))
      (node (ref "U4") (pin "54") (pinfunction "PF14_54") (pintype "bidirectional"))
    )
    (net (code "82") (name "/PF15") (class "Default")
      (node (ref "IC3") (pin "22") (pinfunction "A9_22") (pintype "input"))
      (node (ref "U4") (pin "55") (pinfunction "PF15_55") (pintype "bidirectional"))
    )
    (net (code "83") (name "/PFO") (class "Default")
      (node (ref "IC3") (pin "1") (pinfunction "A0_1") (pintype "input"))
    )
    (net (code "84") (name "/PG0") (class "Default")
      (node (ref "IC3") (pin "23") (pinfunction "A10_23") (pintype "input"))
      (node (ref "U4") (pin "56") (pinfunction "PG0_56") (pintype "bidirectional"))
    )
    (net (code "85") (name "/PG1") (class "Default")
      (node (ref "IC3") (pin "24") (pinfunction "A11_24") (pintype "input"))
      (node (ref "U4") (pin "57") (pinfunction "PG1_57") (pintype "bidirectional"))
    )
    (net (code "86") (name "/PG2") (class "Default")
      (node (ref "IC3") (pin "25") (pinfunction "A12_25") (pintype "input"))
      (node (ref "U4") (pin "87") (pinfunction "PG2_87") (pintype "bidirectional"))
    )
    (net (code "87") (name "/PG3") (class "Default")
      (node (ref "IC3") (pin "26") (pinfunction "A13_26") (pintype "input"))
      (node (ref "U4") (pin "88") (pinfunction "PG3_88") (pintype "bidirectional"))
    )
    (net (code "88") (name "/PG4") (class "Default")
      (node (ref "IC3") (pin "27") (pinfunction "A14_27") (pintype "input"))
      (node (ref "U4") (pin "89") (pinfunction "PG4_89") (pintype "bidirectional"))
    )
    (net (code "89") (name "/PG5") (class "Default")
      (node (ref "IC3") (pin "42") (pinfunction "A15_42") (pintype "input"))
      (node (ref "U4") (pin "90") (pinfunction "PG5_90") (pintype "bidirectional"))
    )
    (net (code "90") (name "/PG9") (class "Default")
      (node (ref "U4") (pin "124") (pinfunction "PG9_124") (pintype "bidirectional"))
    )
    (net (code "91") (name "/PG10") (class "Default")
      (node (ref "IC3") (pin "6") (pinfunction "*CE_6") (pintype "bidirectional"))
      (node (ref "R10") (pin "1") (pinfunction "1_1") (pintype "passive"))
      (node (ref "U4") (pin "125") (pinfunction "PG10_125") (pintype "bidirectional"))
    )
    (net (code "92") (name "/R_IN") (class "Default")
      (node (ref "C17") (pin "+") (pinfunction "+_+") (pintype "passive"))
      (node (ref "C17") (pin "-") (pinfunction "-_-") (pintype "passive"))
      (node (ref "IC2") (pin "6") (pinfunction "-IN_6") (pintype "input"))
      (node (ref "IC2") (pin "7") (pinfunction "OUT_7") (pintype "output"))
      (node (ref "R8") (pin "2") (pinfunction "2_2") (pintype "passive"))
      (node (ref "U2") (pin "P$19") (pinfunction "RLINEIN_P$19") (pintype "input"))
    )
    (net (code "93") (name "/R_OUT") (class "Default")
      (node (ref "C701") (pin "+") (pinfunction "+_+") (pintype "passive"))
      (node (ref "JP7") (pin "2") (pinfunction "2_2") (pintype "passive"))
      (node (ref "U2") (pin "P$13") (pinfunction "ROUT_P$13") (pintype "output"))
    )
    (net (code "94") (name "/SWCLK") (class "Default")
      (node (ref "SWD") (pin "2") (pinfunction "2_2") (pintype "passive"))
      (node (ref "U4") (pin "109") (pinfunction "PA14_109") (pintype "bidirectional"))
    )
    (net (code "95") (name "/SWDIO") (class "Default")
      (node (ref "SWD") (pin "4") (pinfunction "4_4") (pintype "passive"))
      (node (ref "U4") (pin "105") (pinfunction "PA13_105") (pintype "bidirectional"))
    )
    (net (code "96") (name "/SWO") (class "Default")
      (node (ref "SWD") (pin "6") (pinfunction "6_6") (pintype "passive"))
      (node (ref "U4") (pin "133") (pinfunction "PB3_133") (pintype "bidirectional"))
    )
    (net (code "97") (name "/UART_CTS") (class "Default")
      (node (ref "UART") (pin "2") (pinfunction "2_2") (pintype "passive"))
    )
    (net (code "98") (name "/UART_RST") (class "Default")
      (node (ref "UART") (pin "6") (pinfunction "6_6") (pintype "passive"))
    )
    (net (code "99") (name "/UART_RX") (class "Default")
      (node (ref "U4") (pin "136") (pinfunction "PB6_136") (pintype "bidirectional"))
      (node (ref "UART") (pin "5") (pinfunction "5_5") (pintype "passive"))
    )
    (net (code "100") (name "/UART_TX") (class "Default")
      (node (ref "U4") (pin "137") (pinfunction "PB7_137") (pintype "bidirectional"))
      (node (ref "UART") (pin "4") (pinfunction "4_4") (pintype "passive"))
    )
    (net (code "101") (name "/USB_DM") (class "Default")
      (node (ref "R5") (pin "2") (pinfunction "2_2") (pintype "passive"))
      (node (ref "U4") (pin "103") (pinfunction "PA11_103") (pintype "bidirectional"))
    )
    (net (code "102") (name "/USB_DP") (class "Default")
      (node (ref "R4") (pin "2") (pinfunction "2_2") (pintype "passive"))
      (node (ref "U4") (pin "104") (pinfunction "PA12_104") (pintype "bidirectional"))
    )
    (net (code "103") (name "/USB_ID") (class "Default")
      (node (ref "U3") (pin "ID") (pinfunction "USBID_ID") (pintype "bidirectional"))
      (node (ref "U4") (pin "102") (pinfunction "PA10_102") (pintype "bidirectional"))
    )
    (net (code "104") (name "/USB_VBUS") (class "Default")
      (node (ref "JP1") (pin "2") (pinfunction "2_2") (pintype "passive"))
      (node (ref "JP9") (pin "2") (pinfunction "2_2") (pintype "passive"))
      (node (ref "U3") (pin "VBUS") (pinfunction "VBUS_VBUS") (pintype "bidirectional"))
      (node (ref "U4") (pin "101") (pinfunction "PA9_101") (pintype "bidirectional"))
    )
    (net (code "105") (name "/VSSA") (class "Default")
      (node (ref "U4") (pin "31") (pinfunction "VSSA_31") (pintype "power_in"))
    )
    (net (code "106") (name "GND") (class "Default")
      (node (ref "C1") (pin "2") (pinfunction "2_2") (pintype "passive"))
      (node (ref "C10") (pin "2") (pinfunction "2_2") (pintype "passive"))
      (node (ref "C11") (pin "2") (pinfunction "2_2") (pintype "passive"))
      (node (ref "C12") (pin "2") (pinfunction "2_2") (pintype "passive"))
      (node (ref "C13") (pin "2") (pinfunction "2_2") (pintype "passive"))
      (node (ref "C15") (pin "-") (pinfunction "-_-") (pintype "passive"))
      (node (ref "C16") (pin "2") (pinfunction "2_2") (pintype "passive"))
      (node (ref "C18") (pin "2") (pinfunction "2_2") (pintype "passive"))
      (node (ref "C19") (pin "2") (pinfunction "2_2") (pintype "passive"))
      (node (ref "C2") (pin "2") (pinfunction "2_2") (pintype "passive"))
      (node (ref "C20") (pin "1") (pinfunction "1_1") (pintype "passive"))
      (node (ref "C21") (pin "2") (pinfunction "2_2") (pintype "passive"))
      (node (ref "C22") (pin "2") (pinfunction "2_2") (pintype "passive"))
      (node (ref "C23") (pin "2") (pinfunction "2_2") (pintype "passive"))
      (node (ref "C24") (pin "2") (pinfunction "2_2") (pintype "passive"))
      (node (ref "C25") (pin "2") (pinfunction "2_2") (pintype "passive"))
      (node (ref "C26") (pin "2") (pinfunction "2_2") (pintype "passive"))
      (node (ref "C27") (pin "2") (pinfunction "2_2") (pintype "passive"))
      (node (ref "C3") (pin "2") (pinfunction "2_2") (pintype "passive"))
      (node (ref "C300") (pin "2") (pinfunction "2_2") (pintype "passive"))
      (node (ref "C301") (pin "2") (pinfunction "2_2") (pintype "passive"))
      (node (ref "C302") (pin "2") (pinfunction "2_2") (pintype "passive"))
      (node (ref "C303") (pin "2") (pinfunction "2_2") (pintype "passive"))
      (node (ref "C304") (pin "2") (pinfunction "2_2") (pintype "passive"))
      (node (ref "C305") (pin "2") (pinfunction "2_2") (pintype "passive"))
      (node (ref "C306") (pin "2") (pinfunction "2_2") (pintype "passive"))
      (node (ref "C307") (pin "2") (pinfunction "2_2") (pintype "passive"))
      (node (ref "C308") (pin "2") (pinfunction "2_2") (pintype "passive"))
      (node (ref "C309") (pin "2") (pinfunction "2_2") (pintype "passive"))
      (node (ref "C4") (pin "2") (pinfunction "2_2") (pintype "passive"))
      (node (ref "C5") (pin "2") (pinfunction "2_2") (pintype "passive"))
      (node (ref "C6") (pin "2") (pinfunction "2_2") (pintype "passive"))
      (node (ref "C602") (pin "2") (pinfunction "2_2") (pintype "passive"))
      (node (ref "C603") (pin "2") (pinfunction "2_2") (pintype "passive"))
      (node (ref "C7") (pin "2") (pinfunction "2_2") (pintype "passive"))
      (node (ref "C8") (pin "2") (pinfunction "2_2") (pintype "passive"))
      (node (ref "C801") (pin "-") (pinfunction "-_-") (pintype "passive"))
      (node (ref "C802") (pin "-") (pinfunction "-_-") (pintype "passive"))
      (node (ref "C9") (pin "2") (pinfunction "2_2") (pintype "passive"))
      (node (ref "D3") (pin "A") (pinfunction "A_A") (pintype "passive"))
      (node (ref "HP") (pin "2") (pinfunction "2_2") (pintype "passive"))
      (node (ref "IC1") (pin "1") (pinfunction "GND_1") (pintype "power_in"))
      (node (ref "IC2") (pin "4") (pinfunction "V-_4") (pintype "power_in"))
      (node (ref "IC3") (pin "12") (pinfunction "GND_12") (pintype "power_in"))
      (node (ref "IC3") (pin "34") (pinfunction "GND_34") (pintype "power_in"))
      (node (ref "J1") (pin "PWR") (pinfunction "PWR_PWR") (pintype "bidirectional"))
      (node (ref "J2") (pin "S") (pinfunction "S_S") (pintype "passive"))
      (node (ref "J3") (pin "S") (pinfunction "S_S") (pintype "passive"))
      (node (ref "J4") (pin "S") (pinfunction "S_S") (pintype "passive"))
      (node (ref "J5") (pin "S") (pinfunction "S_S") (pintype "passive"))
      (node (ref "JP22") (pin "2") (pinfunction "2_2") (pintype "passive"))
      (node (ref "JP8") (pin "2") (pinfunction "2_2") (pintype "passive"))
      (node (ref "LED1") (pin "C") (pinfunction "C_C") (pintype "passive"))
      (node (ref "LED2") (pin "C") (pinfunction "C_C") (pintype "passive"))
      (node (ref "LED3") (pin "K") (pinfunction "C_K") (pintype "passive"))
      (node (ref "MIC") (pin "2") (pinfunction "2_2") (pintype "passive"))
      (node (ref "POT1") (pin "1") (pinfunction "1_1") (pintype "bidirectional"))
      (node (ref "POT1") (pin "P$5") (pinfunction "P$1_P$5") (pintype "bidirectional"))
      (node (ref "POT1") (pin "P$6") (pinfunction "P$1_P$6") (pintype "bidirectional"))
      (node (ref "POT2") (pin "1") (pinfunction "1_1") (pintype "bidirectional"))
      (node (ref "POT2") (pin "P$5") (pinfunction "P$1_P$5") (pintype "bidirectional"))
      (node (ref "POT2") (pin "P$6") (pinfunction "P$1_P$6") (pintype "bidirectional"))
      (node (ref "POT3") (pin "1") (pinfunction "1_1") (pintype "bidirectional"))
      (node (ref "POT3") (pin "P$5") (pinfunction "P$1_P$5") (pintype "bidirectional"))
      (node (ref "POT3") (pin "P$6") (pinfunction "P$1_P$6") (pintype "bidirectional"))
      (node (ref "POT4") (pin "1") (pinfunction "1_1") (pintype "bidirectional"))
      (node (ref "POT4") (pin "P$5") (pinfunction "P$1_P$5") (pintype "bidirectional"))
      (node (ref "POT4") (pin "P$6") (pinfunction "P$1_P$6") (pintype "bidirectional"))
      (node (ref "R3") (pin "1") (pinfunction "1_1") (pintype "passive"))
      (node (ref "R606") (pin "1") (pinfunction "1_1") (pintype "passive"))
      (node (ref "R607") (pin "1") (pinfunction "1_1") (pintype "passive"))
      (node (ref "R700") (pin "1") (pinfunction "1_1") (pintype "passive"))
      (node (ref "R701") (pin "1") (pinfunction "1_1") (pintype "passive"))
      (node (ref "R9") (pin "2") (pinfunction "2_2") (pintype "passive"))
      (node (ref "SWD") (pin "3") (pinfunction "3_3") (pintype "passive"))
      (node (ref "U2") (pin "P$11") (pinfunction "HPGND_P$11") (pintype "power_in"))
      (node (ref "U2") (pin "P$15") (pinfunction "AGND_P$15") (pintype "power_in"))
      (node (ref "U2") (pin "P$21") (pinfunction "MODE_P$21") (pintype "input"))
      (node (ref "U2") (pin "P$22") (pinfunction "CSB_P$22") (pintype "input"))
      (node (ref "U2") (pin "P$28") (pinfunction "DGND_P$28") (pintype "power_in"))
      (node (ref "U3") (pin "GND") (pinfunction "GND_GND") (pintype "bidirectional"))
      (node (ref "U4") (pin "107") (pinfunction "VSS_5_107") (pintype "power_in"))
      (node (ref "U4") (pin "120") (pinfunction "VSS_120") (pintype "power_in"))
      (node (ref "U4") (pin "130") (pinfunction "VSS_2_130") (pintype "power_in"))
      (node (ref "U4") (pin "17") (pinfunction "VSS_2_17") (pintype "power_in"))
      (node (ref "U4") (pin "38") (pinfunction "VSS_3_38") (pintype "power_in"))
      (node (ref "U4") (pin "51") (pinfunction "VSS_4_51") (pintype "power_in"))
      (node (ref "U4") (pin "61") (pinfunction "VSS_61") (pintype "power_in"))
      (node (ref "U4") (pin "83") (pinfunction "VSS_3_83") (pintype "power_in"))
      (node (ref "U4") (pin "94") (pinfunction "VSS_4_94") (pintype "power_in"))
      (node (ref "UART") (pin "1") (pinfunction "1_1") (pintype "passive"))
    )
    (net (code "107") (name "Net-(C15-Pad+)") (class "Default")
      (node (ref "C15") (pin "+") (pinfunction "+_+") (pintype "passive"))
      (node (ref "C16") (pin "1") (pinfunction "1_1") (pintype "passive"))
      (node (ref "R3") (pin "2") (pinfunction "2_2") (pintype "passive"))
      (node (ref "R600") (pin "1") (pinfunction "1_1") (pintype "passive"))
      (node (ref "R601") (pin "1") (pinfunction "1_1") (pintype "passive"))
      (node (ref "R7") (pin "1") (pinfunction "1_1") (pintype "passive"))
    )
    (net (code "108") (name "Net-(C600-Pad+)") (class "Default")
      (node (ref "C600") (pin "+") (pinfunction "+_+") (pintype "passive"))
      (node (ref "R603") (pin "2") (pinfunction "2_2") (pintype "passive"))
    )
    (net (code "109") (name "Net-(C600-Pad-)") (class "Default")
      (node (ref "C600") (pin "-") (pinfunction "-_-") (pintype "passive"))
      (node (ref "L600") (pin "1") (pinfunction "1_1") (pintype "passive"))
      (node (ref "R606") (pin "2") (pinfunction "2_2") (pintype "passive"))
    )
    (net (code "110") (name "Net-(C601-Pad+)") (class "Default")
      (node (ref "C601") (pin "+") (pinfunction "+_+") (pintype "passive"))
      (node (ref "R602") (pin "2") (pinfunction "2_2") (pintype "passive"))
    )
    (net (code "111") (name "Net-(C601-Pad-)") (class "Default")
      (node (ref "C601") (pin "-") (pinfunction "-_-") (pintype "passive"))
      (node (ref "L601") (pin "1") (pinfunction "1_1") (pintype "passive"))
      (node (ref "R607") (pin "2") (pinfunction "2_2") (pintype "passive"))
    )
    (net (code "112") (name "Net-(C700-Pad-)") (class "Default")
      (node (ref "C700") (pin "-") (pinfunction "-_-") (pintype "passive"))
      (node (ref "R701") (pin "2") (pinfunction "2_2") (pintype "passive"))
      (node (ref "R703") (pin "1") (pinfunction "1_1") (pintype "passive"))
    )
    (net (code "113") (name "Net-(C701-Pad-)") (class "Default")
      (node (ref "C701") (pin "-") (pinfunction "-_-") (pintype "passive"))
      (node (ref "R700") (pin "2") (pinfunction "2_2") (pintype "passive"))
      (node (ref "R702") (pin "1") (pinfunction "1_1") (pintype "passive"))
    )
    (net (code "114") (name "Net-(F3-Pad1)") (class "Default")
      (node (ref "F3") (pin "1") (pinfunction "1_1") (pintype "bidirectional"))
      (node (ref "J1") (pin "GND") (pinfunction "GND_GND") (pintype "bidirectional"))
    )
    (net (code "115") (name "Net-(IC2A-+IN)") (class "Default")
      (node (ref "IC2") (pin "3") (pinfunction "+IN_3") (pintype "input"))
      (node (ref "JP6") (pin "2") (pinfunction "2_2") (pintype "passive"))
      (node (ref "R600") (pin "2") (pinfunction "2_2") (pintype "passive"))
      (node (ref "R603") (pin "1") (pinfunction "1_1") (pintype "passive"))
    )
    (net (code "116") (name "Net-(IC2B-+IN)") (class "Default")
      (node (ref "IC2") (pin "5") (pinfunction "+IN_5") (pintype "input"))
      (node (ref "JP6") (pin "1") (pinfunction "1_1") (pintype "passive"))
      (node (ref "R601") (pin "2") (pinfunction "2_2") (pintype "passive"))
      (node (ref "R602") (pin "1") (pinfunction "1_1") (pintype "passive"))
    )
    (net (code "117") (name "Net-(J1-PadGNDBREAK)") (class "Default")
      (node (ref "J1") (pin "GNDBREAK") (pinfunction "GNDBREAK_GNDBREAK") (pintype "bidirectional"))
      (node (ref "JP9") (pin "1") (pinfunction "1_1") (pintype "passive"))
    )
    (net (code "118") (name "Net-(J2-PadT)") (class "Default")
      (node (ref "J2") (pin "T") (pinfunction "T_T") (pintype "passive"))
      (node (ref "R703") (pin "2") (pinfunction "2_2") (pintype "passive"))
    )
    (net (code "119") (name "Net-(J3-PadT)") (class "Default")
      (node (ref "J3") (pin "T") (pinfunction "T_T") (pintype "passive"))
      (node (ref "R702") (pin "2") (pinfunction "2_2") (pintype "passive"))
    )
    (net (code "120") (name "Net-(LED1-PadA)") (class "Default")
      (node (ref "LED1") (pin "A") (pinfunction "A_A") (pintype "passive"))
      (node (ref "R11") (pin "2") (pinfunction "2_2") (pintype "passive"))
    )
    (net (code "121") (name "Net-(LED2-PadA)") (class "Default")
      (node (ref "LED2") (pin "A") (pinfunction "A_A") (pintype "passive"))
      (node (ref "R12") (pin "2") (pinfunction "2_2") (pintype "passive"))
    )
    (net (code "122") (name "Net-(LED3-PadA)") (class "Default")
      (node (ref "LED3") (pin "A") (pinfunction "A_A") (pintype "passive"))
      (node (ref "R13") (pin "2") (pinfunction "2_2") (pintype "passive"))
    )
    (net (code "123") (name "Net-(R4-Pad1)") (class "Default")
      (node (ref "R4") (pin "1") (pinfunction "1_1") (pintype "passive"))
      (node (ref "U3") (pin "D+") (pinfunction "D+_D+") (pintype "bidirectional"))
    )
    (net (code "124") (name "Net-(R5-Pad1)") (class "Default")
      (node (ref "R5") (pin "1") (pinfunction "1_1") (pintype "passive"))
      (node (ref "U3") (pin "D-") (pinfunction "D-_D-") (pintype "bidirectional"))
    )
    (net (code "125") (name "Net-(U2-LHPOUT)") (class "Default")
      (node (ref "HP") (pin "3") (pinfunction "3_3") (pintype "passive"))
      (node (ref "U2") (pin "P$9") (pinfunction "LHPOUT_P$9") (pintype "output"))
    )
    (net (code "126") (name "Net-(U2-MICBIAS)") (class "Default")
      (node (ref "MIC") (pin "3") (pinfunction "3_3") (pintype "passive"))
      (node (ref "U2") (pin "P$17") (pinfunction "MICBIAS_P$17") (pintype "output"))
    )
    (net (code "127") (name "Net-(U2-MICIN)") (class "Default")
      (node (ref "MIC") (pin "1") (pinfunction "1_1") (pintype "passive"))
      (node (ref "U2") (pin "P$18") (pinfunction "MICIN_P$18") (pintype "input"))
    )
    (net (code "128") (name "Net-(U2-RHPOUT)") (class "Default")
      (node (ref "HP") (pin "1") (pinfunction "1_1") (pintype "passive"))
      (node (ref "U2") (pin "P$10") (pinfunction "RHPOUT_P$10") (pintype "output"))
    )
    (net (code "129") (name "Net-(U4A-PH0)") (class "Default")
      (node (ref "C22") (pin "1") (pinfunction "1_1") (pintype "passive"))
      (node (ref "Q2") (pin "1") (pinfunction "1_1") (pintype "passive"))
      (node (ref "U4") (pin "23") (pinfunction "PH0_23") (pintype "bidirectional"))
    )
    (net (code "130") (name "Net-(U4A-PH1)") (class "Default")
      (node (ref "C23") (pin "1") (pinfunction "1_1") (pintype "passive"))
      (node (ref "Q2") (pin "2") (pinfunction "2_2") (pintype "passive"))
      (node (ref "U4") (pin "24") (pinfunction "PH1_24") (pintype "bidirectional"))
    )
    (net (code "131") (name "Net-(U4A-VCAP_1)") (class "Default")
      (node (ref "C20") (pin "2") (pinfunction "2_2") (pintype "passive"))
      (node (ref "U4") (pin "71") (pinfunction "VCAP_1_71") (pintype "passive"))
    )
    (net (code "132") (name "Net-(U4A-VDDA)") (class "Default")
      (node (ref "C18") (pin "1") (pinfunction "1_1") (pintype "passive"))
      (node (ref "C19") (pin "1") (pinfunction "1_1") (pintype "passive"))
      (node (ref "L3") (pin "1") (pinfunction "1_1") (pintype "passive"))
      (node (ref "U4") (pin "33") (pinfunction "VDDA_33") (pintype "power_in"))
    )
    (net (code "133") (name "Net-(U4B-VCAP_2)") (class "Default")
      (node (ref "C21") (pin "1") (pinfunction "1_1") (pintype "passive"))
      (node (ref "U4") (pin "106") (pinfunction "VCAP_2_106") (pintype "passive"))
    )
    (net (code "134") (name "VCC{slash}2") (class "Default")
      (node (ref "C308") (pin "1") (pinfunction "1_1") (pintype "passive"))
      (node (ref "C309") (pin "1") (pinfunction "1_1") (pintype "passive"))
      (node (ref "R2") (pin "1") (pinfunction "1_1") (pintype "passive"))
      (node (ref "R8") (pin "1") (pinfunction "1_1") (pintype "passive"))
      (node (ref "U2") (pin "P$16") (pinfunction "VMID_P$16") (pintype "output"))
    )
    (net (code "135") (name "VDD") (class "Default")
      (node (ref "C13") (pin "1") (pinfunction "1_1") (pintype "passive"))
      (node (ref "C302") (pin "1") (pinfunction "1_1") (pintype "passive"))
      (node (ref "C303") (pin "1") (pinfunction "1_1") (pintype "passive"))
      (node (ref "JP8") (pin "1") (pinfunction "1_1") (pintype "passive"))
      (node (ref "R6") (pin "2") (pinfunction "2_2") (pintype "passive"))
      (node (ref "U2") (pin "P$14") (pinfunction "AVDD_P$14") (pintype "power_in"))
    )
    (net (code "136") (name "unconnected-(C14-Pad+)") (class "Default")
      (node (ref "C14") (pin "+") (pinfunction "+_+") (pintype "passive"))
    )
    (net (code "137") (name "unconnected-(J2-PadR)") (class "Default")
      (node (ref "J2") (pin "R") (pinfunction "R_R") (pintype "passive"))
    )
    (net (code "138") (name "unconnected-(J2-PadRN)") (class "Default")
      (node (ref "J2") (pin "RN") (pinfunction "RN_RN") (pintype "passive"))
    )
    (net (code "139") (name "unconnected-(J2-PadSN)") (class "Default")
      (node (ref "J2") (pin "SN") (pinfunction "SN_SN") (pintype "passive"))
    )
    (net (code "140") (name "unconnected-(J2-PadTN)") (class "Default")
      (node (ref "J2") (pin "TN") (pinfunction "TN_TN") (pintype "passive"))
    )
    (net (code "141") (name "unconnected-(J3-PadR)") (class "Default")
      (node (ref "J3") (pin "R") (pinfunction "R_R") (pintype "passive"))
    )
    (net (code "142") (name "unconnected-(J3-PadRN)") (class "Default")
      (node (ref "J3") (pin "RN") (pinfunction "RN_RN") (pintype "passive"))
    )
    (net (code "143") (name "unconnected-(J3-PadSN)") (class "Default")
      (node (ref "J3") (pin "SN") (pinfunction "SN_SN") (pintype "passive"))
    )
    (net (code "144") (name "unconnected-(J3-PadTN)") (class "Default")
      (node (ref "J3") (pin "TN") (pinfunction "TN_TN") (pintype "passive"))
    )
    (net (code "145") (name "unconnected-(J4-PadR)") (class "Default")
      (node (ref "J4") (pin "R") (pinfunction "R_R") (pintype "passive"))
    )
    (net (code "146") (name "unconnected-(J4-PadRN)") (class "Default")
      (node (ref "J4") (pin "RN") (pinfunction "RN_RN") (pintype "passive"))
    )
    (net (code "147") (name "unconnected-(J4-PadSN)") (class "Default")
      (node (ref "J4") (pin "SN") (pinfunction "SN_SN") (pintype "passive"))
    )
    (net (code "148") (name "unconnected-(J4-PadTN)") (class "Default")
      (node (ref "J4") (pin "TN") (pinfunction "TN_TN") (pintype "passive"))
    )
    (net (code "149") (name "unconnected-(J5-PadR)") (class "Default")
      (node (ref "J5") (pin "R") (pinfunction "R_R") (pintype "passive"))
    )
    (net (code "150") (name "unconnected-(J5-PadRN)") (class "Default")
      (node (ref "J5") (pin "RN") (pinfunction "RN_RN") (pintype "passive"))
    )
    (net (code "151") (name "unconnected-(J5-PadSN)") (class "Default")
      (node (ref "J5") (pin "SN") (pinfunction "SN_SN") (pintype "passive"))
    )
    (net (code "152") (name "unconnected-(J5-PadTN)") (class "Default")
      (node (ref "J5") (pin "TN") (pinfunction "TN_TN") (pintype "passive"))
    )
    (net (code "153") (name "unconnected-(J6-PadR)") (class "Default")
      (node (ref "J6") (pin "R") (pinfunction "R_R") (pintype "passive"))
    )
    (net (code "154") (name "unconnected-(J6-PadRN)") (class "Default")
      (node (ref "J6") (pin "RN") (pinfunction "RN_RN") (pintype "passive"))
    )
    (net (code "155") (name "unconnected-(J6-PadS)") (class "Default")
      (node (ref "J6") (pin "S") (pinfunction "S_S") (pintype "passive"))
    )
    (net (code "156") (name "unconnected-(J6-PadSN)") (class "Default")
      (node (ref "J6") (pin "SN") (pinfunction "SN_SN") (pintype "passive"))
    )
    (net (code "157") (name "unconnected-(J6-PadT)") (class "Default")
      (node (ref "J6") (pin "T") (pinfunction "T_T") (pintype "passive"))
    )
    (net (code "158") (name "unconnected-(J6-PadTN)") (class "Default")
      (node (ref "J6") (pin "TN") (pinfunction "TN_TN") (pintype "passive"))
    )
    (net (code "159") (name "unconnected-(U2-XTO-PadP$26)") (class "Default")
      (node (ref "U2") (pin "P$26") (pinfunction "XTO_P$26") (pintype "output"))
    )
    (net (code "160") (name "unconnected-(U4A-PE2-Pad1)") (class "Default")
      (node (ref "U4") (pin "1") (pinfunction "PE2_1") (pintype "bidirectional"))
    )
    (net (code "161") (name "unconnected-(U4A-PE3-Pad2)") (class "Default")
      (node (ref "U4") (pin "2") (pinfunction "PE3_2") (pintype "bidirectional"))
    )
    (net (code "162") (name "unconnected-(U4A-PE4-Pad3)") (class "Default")
      (node (ref "U4") (pin "3") (pinfunction "PE4_3") (pintype "bidirectional"))
    )
    (net (code "163") (name "unconnected-(U4A-PE5-Pad4)") (class "Default")
      (node (ref "U4") (pin "4") (pinfunction "PE5_4") (pintype "bidirectional"))
    )
    (net (code "164") (name "unconnected-(U4A-PE6-Pad5)") (class "Default")
      (node (ref "U4") (pin "5") (pinfunction "PE6_5") (pintype "bidirectional"))
    )
    (net (code "165") (name "unconnected-(U4A-PF6-Pad18)") (class "Default")
      (node (ref "U4") (pin "18") (pinfunction "PF6_18") (pintype "bidirectional"))
    )
    (net (code "166") (name "unconnected-(U4A-PF7-Pad19)") (class "Default")
      (node (ref "U4") (pin "19") (pinfunction "PF7_19") (pintype "bidirectional"))
    )
    (net (code "167") (name "unconnected-(U4A-PF8-Pad20)") (class "Default")
      (node (ref "U4") (pin "20") (pinfunction "PF8_20") (pintype "bidirectional"))
    )
    (net (code "168") (name "unconnected-(U4A-PF9-Pad21)") (class "Default")
      (node (ref "U4") (pin "21") (pinfunction "PF9_21") (pintype "bidirectional"))
    )
    (net (code "169") (name "unconnected-(U4A-PF10-Pad22)") (class "Default")
      (node (ref "U4") (pin "22") (pinfunction "PF10_22") (pintype "bidirectional"))
    )
    (net (code "170") (name "unconnected-(U4A-PF11-Pad49)") (class "Default")
      (node (ref "U4") (pin "49") (pinfunction "PF11_49") (pintype "bidirectional"))
    )
    (net (code "171") (name "unconnected-(U4A-VREF+-Pad32)") (class "Default")
      (node (ref "U4") (pin "32") (pinfunction "VREF+_32") (pintype "passive"))
    )
    (net (code "172") (name "unconnected-(U4B-PD3-Pad117)") (class "Default")
      (node (ref "U4") (pin "117") (pinfunction "PD3_117") (pintype "bidirectional"))
    )
    (net (code "173") (name "unconnected-(U4B-PD6-Pad122)") (class "Default")
      (node (ref "U4") (pin "122") (pinfunction "PD6_122") (pintype "bidirectional"))
    )
    (net (code "174") (name "unconnected-(U4B-PD7-Pad123)") (class "Default")
      (node (ref "U4") (pin "123") (pinfunction "PD7_123") (pintype "bidirectional"))
    )
    (net (code "175") (name "unconnected-(U4B-PDR_ON-Pad143)") (class "Default")
      (node (ref "U4") (pin "143") (pinfunction "PDR_ON_143") (pintype "passive"))
    )
    (net (code "176") (name "unconnected-(U4B-PG6-Pad91)") (class "Default")
      (node (ref "U4") (pin "91") (pinfunction "PG6_91") (pintype "bidirectional"))
    )
    (net (code "177") (name "unconnected-(U4B-PG7-Pad92)") (class "Default")
      (node (ref "U4") (pin "92") (pinfunction "PG7_92") (pintype "bidirectional"))
    )
    (net (code "178") (name "unconnected-(U4B-PG8-Pad93)") (class "Default")
      (node (ref "U4") (pin "93") (pinfunction "PG8_93") (pintype "bidirectional"))
    )
    (net (code "179") (name "unconnected-(U4B-PG11-Pad126)") (class "Default")
      (node (ref "U4") (pin "126") (pinfunction "PG11_126") (pintype "bidirectional"))
    )
    (net (code "180") (name "unconnected-(U4B-PG12-Pad127)") (class "Default")
      (node (ref "U4") (pin "127") (pinfunction "PG12_127") (pintype "bidirectional"))
    )
    (net (code "181") (name "unconnected-(U4B-PG13-Pad128)") (class "Default")
      (node (ref "U4") (pin "128") (pinfunction "PG13_128") (pintype "bidirectional"))
    )
    (net (code "182") (name "unconnected-(U4B-PG14-Pad129)") (class "Default")
      (node (ref "U4") (pin "129") (pinfunction "PG14_129") (pintype "bidirectional"))
    )
    (net (code "183") (name "unconnected-(U4B-PG15-Pad132)") (class "Default")
      (node (ref "U4") (pin "132") (pinfunction "PG15_132") (pintype "bidirectional"))
    )
  )
)
